# power.net
KiCad netlist of a schematic drawn in Altium Designer
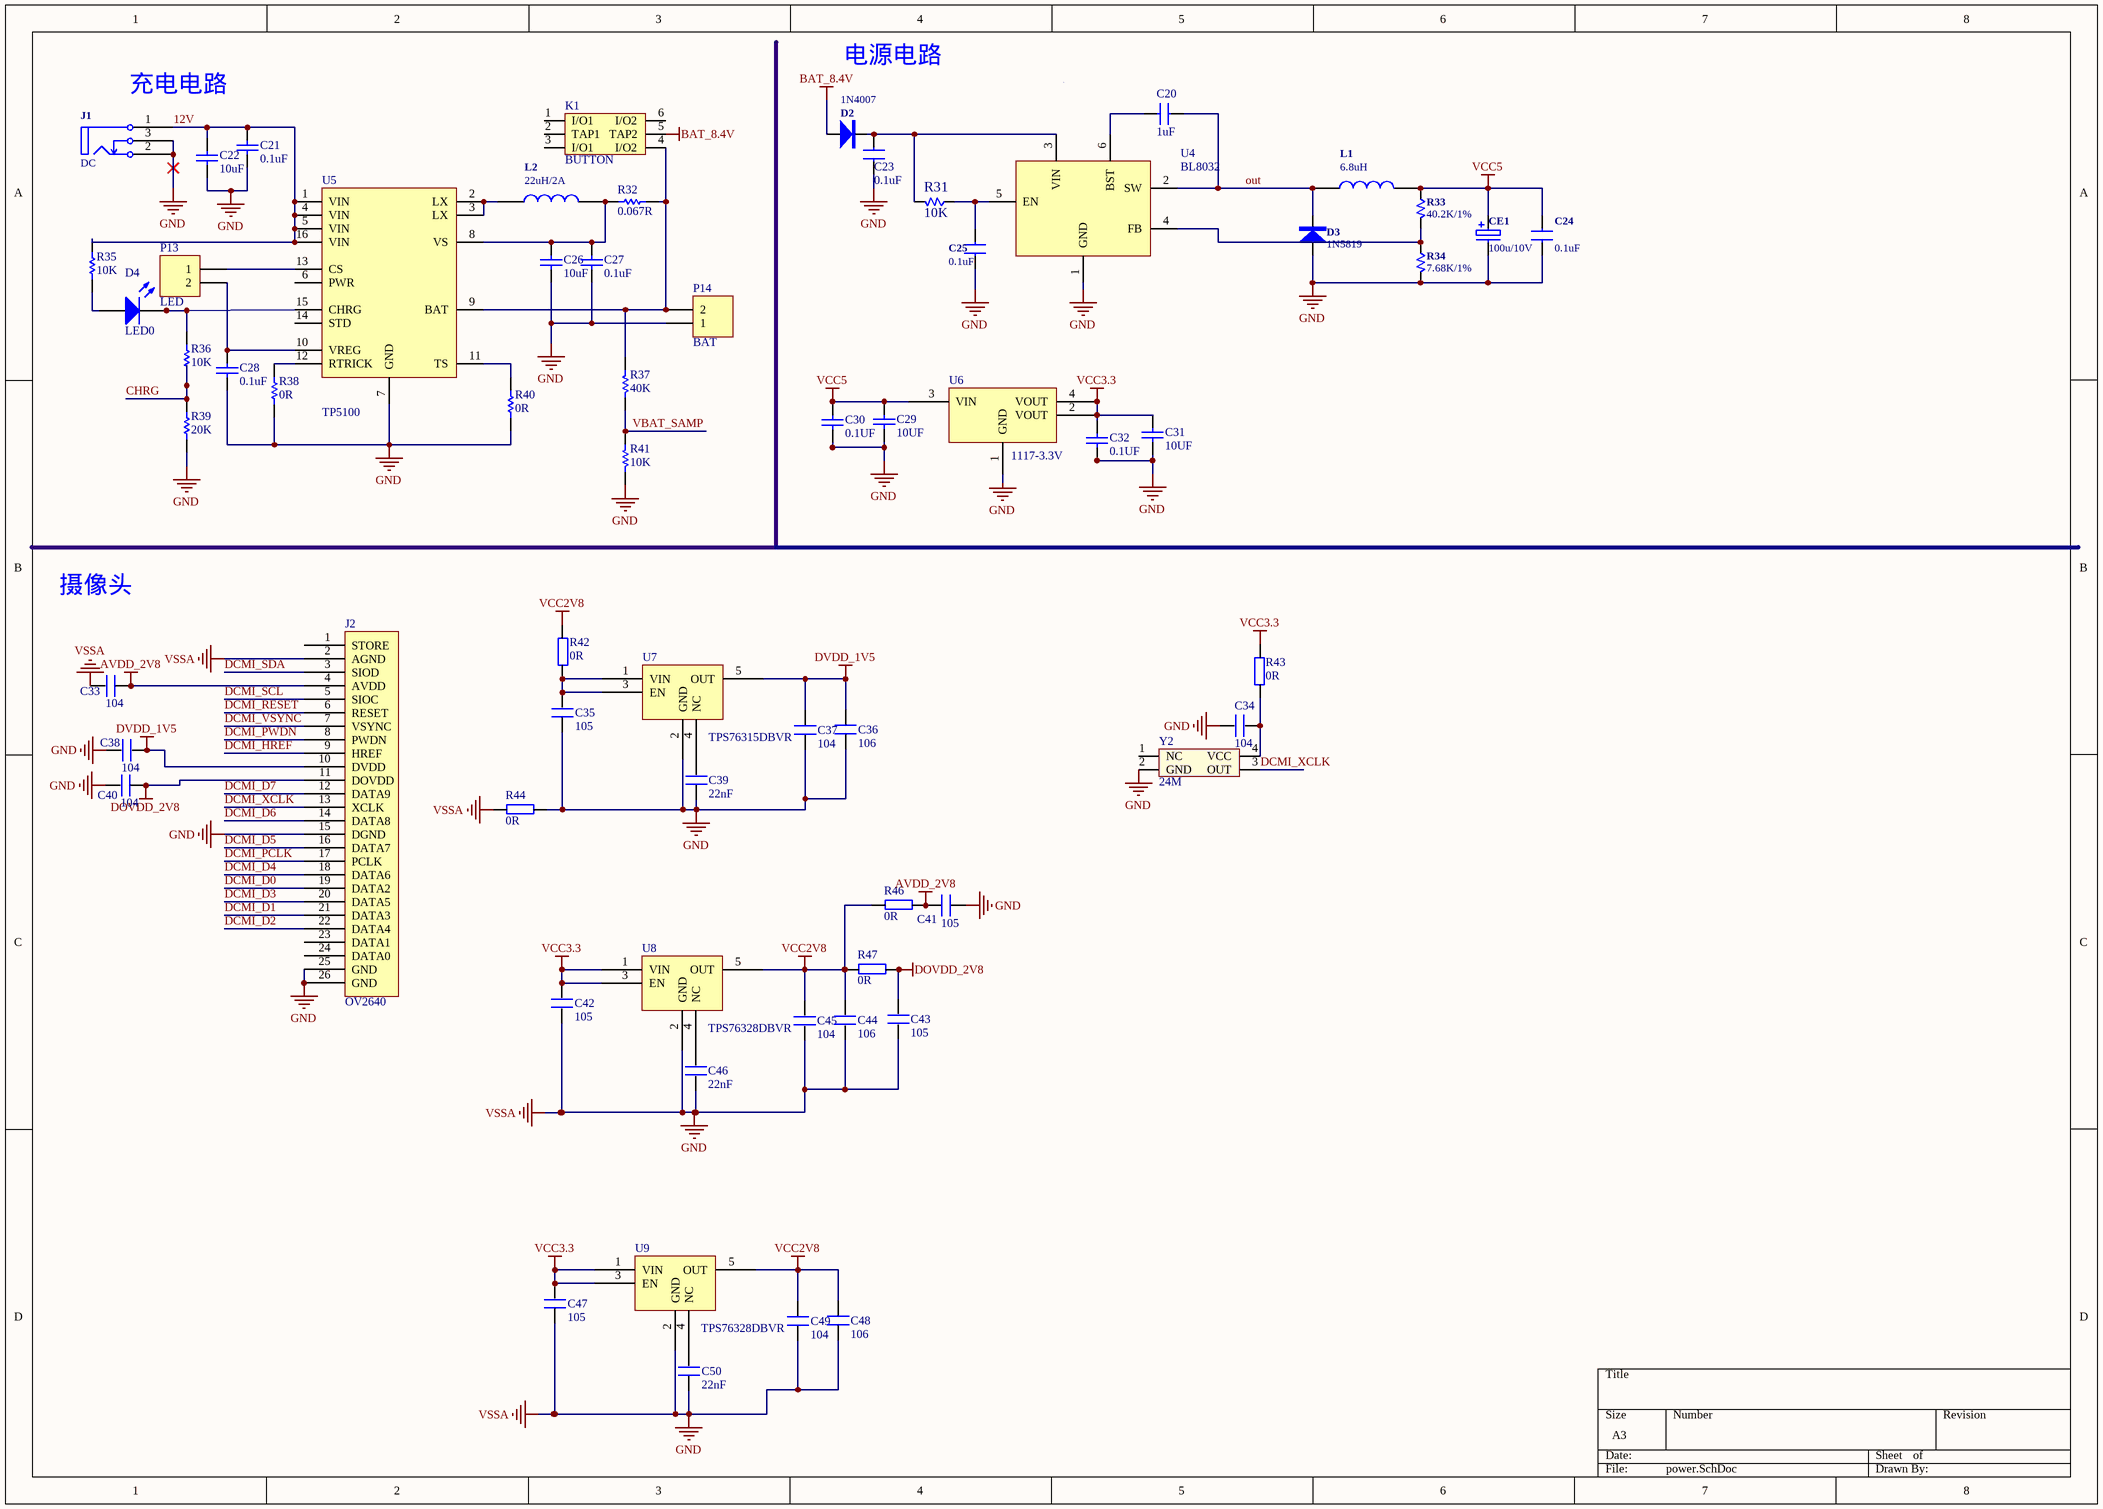
[diagram p0: power.SchDoc]

(export (version "E")
  (design (tool "Eeschema 10.0.6"))
  (components
    (comp (ref "C20")
      (value "1uF")
      (footprint "0603c")
      (description "Capacitor")
      (libsource (lib "") (part "CAP_1"))
    )
    (comp (ref "C21")
      (value "0.1uF")
      (footprint "0603C")
      (description "Capacitor")
      (fields (field (name "PUBLISHER") "Altium Limited"))
      (libsource (lib "STM32") (part "CAP"))
    )
    (comp (ref "C22")
      (value "10uF")
      (footprint "0805C")
      (description "Capacitor")
      (fields (field (name "PUBLISHER") "Altium Limited"))
      (libsource (lib "Miscellaneous Devices") (part "Cap"))
    )
    (comp (ref "C23")
      (value "0.1uF")
      (footprint "C0603")
      (description "Capacitor")
      (libsource (lib "*") (part "CAP"))
    )
    (comp (ref "C24")
      (value "0.1uF")
      (footprint "C0603")
      (description "Capacitor")
      (libsource (lib "*") (part "CAP"))
    )
    (comp (ref "C25")
      (value "0.1uF")
      (footprint "C0603")
      (description "Capacitor")
      (libsource (lib "*") (part "CAP"))
    )
    (comp (ref "C26")
      (value "10uF")
      (footprint "0603C")
      (description "Capacitor")
      (fields (field (name "PUBLISHER") "Altium Limited"))
      (libsource (lib "STM32") (part "CAP"))
    )
    (comp (ref "C27")
      (value "0.1uF")
      (footprint "0603C")
      (description "Capacitor")
      (fields (field (name "PUBLISHER") "Altium Limited"))
      (libsource (lib "STM32") (part "CAP"))
    )
    (comp (ref "C28")
      (value "0.1uF")
      (footprint "0603C")
      (description "Capacitor")
      (fields (field (name "PUBLISHER") "Altium Limited"))
      (libsource (lib "STM32") (part "CAP"))
    )
    (comp (ref "C29")
      (value "10UF")
      (footprint "0603C")
      (description "Capacitor")
      (fields (field (name "Comment") "Cap") (field (name "PUBLISHER") "Altium Limited"))
      (libsource (lib "Miscellaneous Devices") (part "Cap"))
    )
    (comp (ref "C30")
      (value "0.1UF")
      (footprint "0603C")
      (description "Capacitor")
      (fields (field (name "Comment") "Cap") (field (name "PUBLISHER") "Altium Limited"))
      (libsource (lib "Miscellaneous Devices") (part "Cap"))
    )
    (comp (ref "C31")
      (value "10UF")
      (footprint "0603C")
      (description "Capacitor")
      (fields (field (name "Comment") "Cap") (field (name "PUBLISHER") "Altium Limited"))
      (libsource (lib "Miscellaneous Devices") (part "Cap"))
    )
    (comp (ref "C32")
      (value "0.1UF")
      (footprint "0603C")
      (description "Capacitor")
      (fields (field (name "Comment") "Cap") (field (name "PUBLISHER") "Altium Limited"))
      (libsource (lib "Miscellaneous Devices") (part "Cap"))
    )
    (comp (ref "C33") (value "104") (footprint "0603P") (libsource (lib "STM32F429核心板封装库") (part "C")))
    (comp (ref "C34") (value "104") (footprint "0603P") (libsource (lib "STM32F429核心板封装库") (part "C")))
    (comp (ref "C35") (value "105") (footprint "0603P") (libsource (lib "STM32F429核心板封装库") (part "C")))
    (comp (ref "C36") (value "106") (footprint "0603P") (libsource (lib "STM32F429核心板封装库") (part "C")))
    (comp (ref "C37") (value "104") (footprint "0603P") (libsource (lib "STM32F429核心板封装库") (part "C")))
    (comp (ref "C38") (value "104") (footprint "0603P") (libsource (lib "STM32F429核心板封装库") (part "C")))
    (comp (ref "C39") (value "22nF") (footprint "0603P") (libsource (lib "STM32F429核心板封装库") (part "C")))
    (comp (ref "C40") (value "104") (footprint "0603P") (libsource (lib "STM32F429核心板封装库") (part "C")))
    (comp (ref "C41") (value "105") (footprint "0603P") (libsource (lib "STM32F429核心板封装库") (part "C")))
    (comp (ref "C42") (value "105") (footprint "0603P") (libsource (lib "STM32F429核心板封装库") (part "C")))
    (comp (ref "C43") (value "105") (footprint "0603P") (libsource (lib "STM32F429核心板封装库") (part "C")))
    (comp (ref "C44") (value "106") (footprint "0603P") (libsource (lib "STM32F429核心板封装库") (part "C")))
    (comp (ref "C45") (value "104") (footprint "0603P") (libsource (lib "STM32F429核心板封装库") (part "C")))
    (comp (ref "C46") (value "22nF") (footprint "0603P") (libsource (lib "STM32F429核心板封装库") (part "C")))
    (comp (ref "C47") (value "105") (footprint "0603P") (libsource (lib "STM32F429核心板封装库") (part "C")))
    (comp (ref "C48") (value "106") (footprint "0603P") (libsource (lib "STM32F429核心板封装库") (part "C")))
    (comp (ref "C49") (value "104") (footprint "0603P") (libsource (lib "STM32F429核心板封装库") (part "C")))
    (comp (ref "C50") (value "22nF") (footprint "0603P") (libsource (lib "STM32F429核心板封装库") (part "C")))
    (comp (ref "CE1") (value "100u/10V") (footprint "C_195") (libsource (lib "*") (part "CE")))
    (comp (ref "D2")
      (value "1N4007")
      (footprint "DO-214AC")
      (description "Diode")
      (libsource (lib "*") (part "D"))
    )
    (comp (ref "D3")
      (value "1N5819")
      (footprint "DO-214AC")
      (description "Diode")
      (libsource (lib "") (part "D_1"))
    )
    (comp (ref "D4")
      (value "LED0")
      (footprint "0603LED")
      (description "Typical INFRARED GaAs LED")
      (fields (field (name "PUBLISHER") "Altium Limited"))
      (libsource (lib "Miscellaneous Devices") (part "LED0"))
    )
    (comp (ref "J1") (value "DC") (footprint "dc5V") (libsource (lib "*") (part "POWERCON")))
    (comp (ref "J2")
      (value "OV2640")
      (footprint "wifi_car:OV2640")
      (libsource (lib "wifi_car") (part "OV2640"))
    )
    (comp (ref "K1")
      (value "BUTTON")
      (footprint "BTN8.5*8.5")
      (libsource (lib "阿波罗STM32F4&F7底板封装库") (part "BUTTON"))
    )
    (comp (ref "L1") (value "6.8uH") (footprint "WE_PD") (libsource (lib "*") (part "INDUCTOR")))
    (comp (ref "L2") (value "22uH/2A") (footprint "WE_PD") (libsource (lib "*") (part "INDUCTOR")))
    (comp (ref "P13")
      (value "LED")
      (footprint "SIP2")
      (description "Header, 2-Pin")
      (fields (field (name "PUBLISHER") "Altium Limited"))
      (libsource (lib "Miscellaneous Connectors") (part "Header 2"))
    )
    (comp (ref "P14")
      (value "BAT")
      (footprint "CON2")
      (description "Header, 2-Pin")
      (fields (field (name "PUBLISHER") "Altium Limited"))
      (libsource (lib "") (part "Header 2_1"))
    )
    (comp (ref "R31")
      (value "10K")
      (footprint "R0603")
      (description "Resistor")
      (libsource (lib "*") (part "R"))
    )
    (comp (ref "R32")
      (value "0.067R")
      (footprint "1206")
      (description "Resistor")
      (fields (field (name "PUBLISHER") "Altium Limited"))
      (libsource (lib "Miscellaneous Devices") (part "Res1"))
    )
    (comp (ref "R33")
      (value "40.2K/1%")
      (footprint "R0603")
      (description "Resistor")
      (libsource (lib "CONNECTOR") (part "R"))
    )
    (comp (ref "R34")
      (value "7.68K/1%")
      (footprint "R0603")
      (description "Resistor")
      (libsource (lib "CONNECTOR") (part "R"))
    )
    (comp (ref "R35")
      (value "10K")
      (footprint "0603C")
      (description "Resistor")
      (fields (field (name "PUBLISHER") "Altium Limited"))
      (libsource (lib "Miscellaneous Devices") (part "Res1"))
    )
    (comp (ref "R36")
      (value "10K")
      (footprint "0603C")
      (description "Resistor")
      (fields (field (name "PUBLISHER") "Altium Limited"))
      (libsource (lib "Miscellaneous Devices") (part "Res1"))
    )
    (comp (ref "R37")
      (value "40K")
      (footprint "0603R")
      (description "Resistor")
      (fields (field (name "PUBLISHER") "Altium Limited"))
      (libsource (lib "STM32") (part "res1"))
    )
    (comp (ref "R38")
      (value "0R")
      (footprint "0603C")
      (description "Resistor")
      (fields (field (name "PUBLISHER") "Altium Limited"))
      (libsource (lib "Miscellaneous Devices") (part "Res1"))
    )
    (comp (ref "R39")
      (value "20K")
      (footprint "0603C")
      (description "Resistor")
      (fields (field (name "PUBLISHER") "Altium Limited"))
      (libsource (lib "Miscellaneous Devices") (part "Res1"))
    )
    (comp (ref "R40")
      (value "0R")
      (footprint "0603R")
      (description "Resistor")
      (fields (field (name "PUBLISHER") "Altium Limited"))
      (libsource (lib "Miscellaneous Devices") (part "Res1"))
    )
    (comp (ref "R41")
      (value "10K")
      (footprint "0603R")
      (description "Resistor")
      (fields (field (name "PUBLISHER") "Altium Limited"))
      (libsource (lib "STM32") (part "res1"))
    )
    (comp (ref "R42") (value "0R") (footprint "0603P") (libsource (lib "STM32F429核心板封装库") (part "R")))
    (comp (ref "R43") (value "0R") (footprint "0603P") (libsource (lib "STM32F429核心板封装库") (part "R")))
    (comp (ref "R44") (value "0R") (footprint "0603P") (libsource (lib "STM32F429核心板封装库") (part "R")))
    (comp (ref "R46") (value "0R") (footprint "0603P") (libsource (lib "STM32F429核心板封装库") (part "R")))
    (comp (ref "R47") (value "0R") (footprint "0603P") (libsource (lib "STM32F429核心板封装库") (part "R")))
    (comp (ref "U4")
      (value "BL8032")
      (footprint "SOT23-6")
      (description "Diode Bridge")
      (libsource (lib "F718_XP_V1.0") (part "BL8032"))
    )
    (comp (ref "U5")
      (value "TP5100")
      (footprint "QFN16(4*4)")
      (description "Capacitor")
      (fields (field (name "PUBLISHER") "Altium Limited"))
      (libsource (lib "ZNXC_V1.0") (part "TP5100"))
    )
    (comp (ref "U6")
      (value "1117-3.3V")
      (footprint "SOT223")
      (description "LDO")
      (fields (field (name "PUBLISHER") "Altium Limited"))
      (libsource (lib "TS-QBF-05") (part "1117"))
    )
    (comp (ref "U7")
      (value "TPS76315DBVR")
      (footprint "wifi_car:TPS763")
      (libsource (lib "wifi_car") (part "TPS763  SOT23-5"))
    )
    (comp (ref "U8")
      (value "TPS76328DBVR")
      (footprint "wifi_car:TPS763")
      (description "TPS76315DBVR")
      (libsource (lib "wifi_car") (part "TPS763  SOT23-5"))
    )
    (comp (ref "U9")
      (value "TPS76328DBVR")
      (footprint "wifi_car:TPS763")
      (description "TPS76315DBVR")
      (libsource (lib "wifi_car") (part "TPS763  SOT23-5"))
    )
    (comp (ref "Y2") (value "24M") (footprint "wifi_car:XTAL_S") (libsource (lib "wifi_car") (part "XTAL_S")))
  )
  (nets
    (net (code "1") (name "/12V") (class "Default")
      (node (ref "C21") (pin "2") (pinfunction "2_2") (pintype "passive"))
      (node (ref "C22") (pin "1") (pinfunction "1_1") (pintype "passive"))
      (node (ref "J1") (pin "1") (pintype "passive"))
      (node (ref "R35") (pin "2") (pinfunction "2_2") (pintype "passive"))
      (node (ref "U5") (pin "1") (pinfunction "VIN_1") (pintype "passive"))
      (node (ref "U5") (pin "16") (pinfunction "VIN_16") (pintype "passive"))
      (node (ref "U5") (pin "4") (pinfunction "VIN_4") (pintype "passive"))
      (node (ref "U5") (pin "5") (pinfunction "VIN_5") (pintype "passive"))
    )
    (net (code "2") (name "/CHRG") (class "Default")
      (node (ref "R36") (pin "1") (pinfunction "1_1") (pintype "passive"))
      (node (ref "R39") (pin "2") (pinfunction "2_2") (pintype "passive"))
    )
    (net (code "3") (name "/DCMI_D0") (class "Default")
      (node (ref "J2") (pin "19") (pinfunction "DATA2_19") (pintype "passive"))
    )
    (net (code "4") (name "/DCMI_D1") (class "Default")
      (node (ref "J2") (pin "21") (pinfunction "DATA3_21") (pintype "passive"))
    )
    (net (code "5") (name "/DCMI_D2") (class "Default")
      (node (ref "J2") (pin "22") (pinfunction "DATA4_22") (pintype "passive"))
    )
    (net (code "6") (name "/DCMI_D3") (class "Default")
      (node (ref "J2") (pin "20") (pinfunction "DATA5_20") (pintype "passive"))
    )
    (net (code "7") (name "/DCMI_D4") (class "Default")
      (node (ref "J2") (pin "18") (pinfunction "DATA6_18") (pintype "passive"))
    )
    (net (code "8") (name "/DCMI_D5") (class "Default")
      (node (ref "J2") (pin "16") (pinfunction "DATA7_16") (pintype "passive"))
    )
    (net (code "9") (name "/DCMI_D6") (class "Default")
      (node (ref "J2") (pin "14") (pinfunction "DATA8_14") (pintype "passive"))
    )
    (net (code "10") (name "/DCMI_D7") (class "Default")
      (node (ref "J2") (pin "12") (pinfunction "DATA9_12") (pintype "passive"))
    )
    (net (code "11") (name "/DCMI_HREF") (class "Default")
      (node (ref "J2") (pin "9") (pinfunction "HREF_9") (pintype "passive"))
    )
    (net (code "12") (name "/DCMI_PCLK") (class "Default")
      (node (ref "J2") (pin "17") (pinfunction "PCLK_17") (pintype "passive"))
    )
    (net (code "13") (name "/DCMI_PWDN") (class "Default")
      (node (ref "J2") (pin "8") (pinfunction "PWDN_8") (pintype "passive"))
    )
    (net (code "14") (name "/DCMI_RESET") (class "Default")
      (node (ref "J2") (pin "6") (pinfunction "RESET_6") (pintype "passive"))
    )
    (net (code "15") (name "/DCMI_SCL") (class "Default")
      (node (ref "J2") (pin "5") (pinfunction "SIOC_5") (pintype "passive"))
    )
    (net (code "16") (name "/DCMI_SDA") (class "Default")
      (node (ref "J2") (pin "3") (pinfunction "SIOD_3") (pintype "passive"))
    )
    (net (code "17") (name "/DCMI_VSYNC") (class "Default")
      (node (ref "J2") (pin "7") (pinfunction "VSYNC_7") (pintype "passive"))
    )
    (net (code "18") (name "/DCMI_XCLK") (class "Default")
      (node (ref "J2") (pin "13") (pinfunction "XCLK_13") (pintype "passive"))
      (node (ref "Y2") (pin "3") (pinfunction "OUT_3") (pintype "passive"))
    )
    (net (code "19") (name "/VBAT_SAMP") (class "Default")
      (node (ref "R37") (pin "2") (pinfunction "2_2") (pintype "passive"))
      (node (ref "R41") (pin "1") (pinfunction "1_1") (pintype "passive"))
    )
    (net (code "20") (name "/out") (class "Default")
      (node (ref "C20") (pin "2") (pinfunction "2_2") (pintype "passive"))
      (node (ref "D3") (pin "2") (pinfunction "K_2") (pintype "passive"))
      (node (ref "L1") (pin "1") (pinfunction "1_1") (pintype "passive"))
      (node (ref "U4") (pin "2") (pinfunction "SW_2") (pintype "passive"))
    )
    (net (code "21") (name "AVDD_2V8") (class "Default")
      (node (ref "C33") (pin "1") (pintype "passive"))
      (node (ref "C41") (pin "1") (pintype "passive"))
      (node (ref "J2") (pin "4") (pinfunction "AVDD_4") (pintype "passive"))
      (node (ref "R46") (pin "1") (pintype "passive"))
    )
    (net (code "22") (name "BAT_8.4V") (class "Default")
      (node (ref "D2") (pin "1") (pinfunction "A_1") (pintype "passive"))
      (node (ref "K1") (pin "5") (pinfunction "TAP2_5") (pintype "passive"))
    )
    (net (code "23") (name "DOVDD_2V8") (class "Default")
      (node (ref "C40") (pin "1") (pintype "passive"))
      (node (ref "C43") (pin "2") (pintype "passive"))
      (node (ref "J2") (pin "11") (pinfunction "DOVDD_11") (pintype "passive"))
      (node (ref "R47") (pin "1") (pintype "passive"))
    )
    (net (code "24") (name "DVDD_1V5") (class "Default")
      (node (ref "C36") (pin "2") (pintype "passive"))
      (node (ref "C37") (pin "2") (pintype "passive"))
      (node (ref "C38") (pin "1") (pintype "passive"))
      (node (ref "J2") (pin "10") (pinfunction "DVDD_10") (pintype "passive"))
      (node (ref "U7") (pin "5") (pinfunction "OUT_5") (pintype "passive"))
    )
    (net (code "25") (name "GND") (class "Default")
      (node (ref "C21") (pin "1") (pinfunction "1_1") (pintype "passive"))
      (node (ref "C22") (pin "2") (pinfunction "2_2") (pintype "passive"))
      (node (ref "C23") (pin "2") (pinfunction "2_2") (pintype "passive"))
      (node (ref "C24") (pin "2") (pinfunction "2_2") (pintype "passive"))
      (node (ref "C25") (pin "2") (pinfunction "2_2") (pintype "passive"))
      (node (ref "C26") (pin "1") (pinfunction "1_1") (pintype "passive"))
      (node (ref "C27") (pin "1") (pinfunction "1_1") (pintype "passive"))
      (node (ref "C28") (pin "1") (pinfunction "1_1") (pintype "passive"))
      (node (ref "C29") (pin "2") (pinfunction "2_2") (pintype "passive"))
      (node (ref "C30") (pin "2") (pinfunction "2_2") (pintype "passive"))
      (node (ref "C31") (pin "2") (pinfunction "2_2") (pintype "passive"))
      (node (ref "C32") (pin "2") (pinfunction "2_2") (pintype "passive"))
      (node (ref "C33") (pin "2") (pintype "passive"))
      (node (ref "C34") (pin "2") (pintype "passive"))
      (node (ref "C35") (pin "1") (pintype "passive"))
      (node (ref "C36") (pin "1") (pintype "passive"))
      (node (ref "C37") (pin "1") (pintype "passive"))
      (node (ref "C38") (pin "2") (pintype "passive"))
      (node (ref "C39") (pin "1") (pintype "passive"))
      (node (ref "C40") (pin "2") (pintype "passive"))
      (node (ref "C41") (pin "2") (pintype "passive"))
      (node (ref "C42") (pin "1") (pintype "passive"))
      (node (ref "C43") (pin "1") (pintype "passive"))
      (node (ref "C44") (pin "1") (pintype "passive"))
      (node (ref "C45") (pin "1") (pintype "passive"))
      (node (ref "C46") (pin "1") (pintype "passive"))
      (node (ref "C47") (pin "1") (pintype "passive"))
      (node (ref "C48") (pin "1") (pintype "passive"))
      (node (ref "C49") (pin "1") (pintype "passive"))
      (node (ref "C50") (pin "1") (pintype "passive"))
      (node (ref "CE1") (pin "2") (pintype "passive"))
      (node (ref "D3") (pin "1") (pinfunction "A_1") (pintype "passive"))
      (node (ref "J1") (pin "2") (pintype "passive"))
      (node (ref "J1") (pin "3") (pintype "passive"))
      (node (ref "J2") (pin "15") (pinfunction "DGND_15") (pintype "passive"))
      (node (ref "J2") (pin "2") (pinfunction "AGND_2") (pintype "passive"))
      (node (ref "J2") (pin "25") (pinfunction "GND_25") (pintype "passive"))
      (node (ref "J2") (pin "26") (pinfunction "GND_26") (pintype "passive"))
      (node (ref "P14") (pin "1") (pinfunction "1_1") (pintype "passive"))
      (node (ref "R34") (pin "2") (pinfunction "2_2") (pintype "passive"))
      (node (ref "R38") (pin "1") (pinfunction "1_1") (pintype "passive"))
      (node (ref "R39") (pin "1") (pinfunction "1_1") (pintype "passive"))
      (node (ref "R40") (pin "1") (pinfunction "1_1") (pintype "passive"))
      (node (ref "R41") (pin "2") (pinfunction "2_2") (pintype "passive"))
      (node (ref "R44") (pin "1") (pintype "passive"))
      (node (ref "R44") (pin "2") (pintype "passive"))
      (node (ref "U4") (pin "1") (pinfunction "GND_1") (pintype "passive"))
      (node (ref "U5") (pin "7") (pinfunction "GND_7") (pintype "passive"))
      (node (ref "U6") (pin "1") (pinfunction "GND_1") (pintype "passive"))
      (node (ref "U7") (pin "2") (pinfunction "GND_2") (pintype "passive"))
      (node (ref "U8") (pin "2") (pinfunction "GND_2") (pintype "passive"))
      (node (ref "U9") (pin "2") (pinfunction "GND_2") (pintype "passive"))
      (node (ref "Y2") (pin "2") (pinfunction "GND_2") (pintype "passive"))
    )
    (net (code "26") (name "Net-(D2-K)") (class "Default")
      (node (ref "C23") (pin "1") (pinfunction "1_1") (pintype "passive"))
      (node (ref "D2") (pin "2") (pinfunction "K_2") (pintype "passive"))
      (node (ref "R31") (pin "2") (pinfunction "2_2") (pintype "passive"))
      (node (ref "U4") (pin "3") (pinfunction "VIN_3") (pintype "passive"))
    )
    (net (code "27") (name "Net-(D4-A)") (class "Default")
      (node (ref "D4") (pin "1") (pinfunction "A_1") (pintype "passive"))
      (node (ref "R35") (pin "1") (pinfunction "1_1") (pintype "passive"))
    )
    (net (code "28") (name "Net-(D4-K)") (class "Default")
      (node (ref "D4") (pin "2") (pinfunction "K_2") (pintype "passive"))
      (node (ref "R36") (pin "2") (pinfunction "2_2") (pintype "passive"))
      (node (ref "U5") (pin "15") (pinfunction "CHRG_15") (pintype "passive"))
    )
    (net (code "29") (name "Net-(L2-Pad1)") (class "Default")
      (node (ref "L2") (pin "1") (pinfunction "1_1") (pintype "passive"))
      (node (ref "U5") (pin "2") (pinfunction "LX_2") (pintype "passive"))
      (node (ref "U5") (pin "3") (pinfunction "LX_3") (pintype "passive"))
    )
    (net (code "30") (name "Net-(U4-BST)") (class "Default")
      (node (ref "C20") (pin "1") (pinfunction "1_1") (pintype "passive"))
      (node (ref "U4") (pin "6") (pinfunction "BST_6") (pintype "passive"))
    )
    (net (code "31") (name "Net-(U4-EN)") (class "Default")
      (node (ref "C25") (pin "1") (pinfunction "1_1") (pintype "passive"))
      (node (ref "R31") (pin "1") (pinfunction "1_1") (pintype "passive"))
      (node (ref "U4") (pin "5") (pinfunction "EN_5") (pintype "passive"))
    )
    (net (code "32") (name "Net-(U4-FB)") (class "Default")
      (node (ref "R33") (pin "2") (pinfunction "2_2") (pintype "passive"))
      (node (ref "R34") (pin "1") (pinfunction "1_1") (pintype "passive"))
      (node (ref "U4") (pin "4") (pinfunction "FB_4") (pintype "passive"))
    )
    (net (code "33") (name "Net-(U5-BAT)") (class "Default")
      (node (ref "K1") (pin "4") (pinfunction "I/O2_4") (pintype "passive"))
      (node (ref "P14") (pin "2") (pinfunction "2_2") (pintype "passive"))
      (node (ref "R32") (pin "1") (pinfunction "1_1") (pintype "passive"))
      (node (ref "R37") (pin "1") (pinfunction "1_1") (pintype "passive"))
      (node (ref "U5") (pin "9") (pinfunction "BAT_9") (pintype "passive"))
    )
    (net (code "34") (name "Net-(U5-CS)") (class "Default")
      (node (ref "P13") (pin "1") (pinfunction "1_1") (pintype "passive"))
      (node (ref "U5") (pin "13") (pinfunction "CS_13") (pintype "passive"))
    )
    (net (code "35") (name "Net-(U5-RTRICK)") (class "Default")
      (node (ref "R38") (pin "2") (pinfunction "2_2") (pintype "passive"))
      (node (ref "U5") (pin "12") (pinfunction "RTRICK_12") (pintype "passive"))
    )
    (net (code "36") (name "Net-(U5-TS)") (class "Default")
      (node (ref "R40") (pin "2") (pinfunction "2_2") (pintype "passive"))
      (node (ref "U5") (pin "11") (pinfunction "TS_11") (pintype "passive"))
    )
    (net (code "37") (name "Net-(U5-VREG)") (class "Default")
      (node (ref "C28") (pin "2") (pinfunction "2_2") (pintype "passive"))
      (node (ref "P13") (pin "2") (pinfunction "2_2") (pintype "passive"))
      (node (ref "U5") (pin "10") (pinfunction "VREG_10") (pintype "passive"))
    )
    (net (code "38") (name "Net-(U5-VS)") (class "Default")
      (node (ref "C26") (pin "2") (pinfunction "2_2") (pintype "passive"))
      (node (ref "C27") (pin "2") (pinfunction "2_2") (pintype "passive"))
      (node (ref "L2") (pin "2") (pinfunction "2_2") (pintype "passive"))
      (node (ref "R32") (pin "2") (pinfunction "2_2") (pintype "passive"))
      (node (ref "U5") (pin "8") (pinfunction "VS_8") (pintype "passive"))
    )
    (net (code "39") (name "Net-(U7-EN)") (class "Default")
      (node (ref "C35") (pin "2") (pintype "passive"))
      (node (ref "R42") (pin "1") (pintype "passive"))
      (node (ref "U7") (pin "1") (pinfunction "VIN_1") (pintype "passive"))
      (node (ref "U7") (pin "3") (pinfunction "EN_3") (pintype "passive"))
    )
    (net (code "40") (name "Net-(U7-NC)") (class "Default")
      (node (ref "C39") (pin "2") (pintype "passive"))
      (node (ref "U7") (pin "4") (pinfunction "NC_4") (pintype "passive"))
    )
    (net (code "41") (name "Net-(U8-NC)") (class "Default")
      (node (ref "C46") (pin "2") (pintype "passive"))
      (node (ref "U8") (pin "4") (pinfunction "NC_4") (pintype "passive"))
    )
    (net (code "42") (name "Net-(U9-NC)") (class "Default")
      (node (ref "C50") (pin "2") (pintype "passive"))
      (node (ref "U9") (pin "4") (pinfunction "NC_4") (pintype "passive"))
    )
    (net (code "43") (name "Net-(Y2-VCC)") (class "Default")
      (node (ref "C34") (pin "1") (pintype "passive"))
      (node (ref "R43") (pin "2") (pintype "passive"))
      (node (ref "Y2") (pin "4") (pinfunction "VCC_4") (pintype "passive"))
    )
    (net (code "44") (name "VCC2V8") (class "Default")
      (node (ref "C44") (pin "2") (pintype "passive"))
      (node (ref "C45") (pin "2") (pintype "passive"))
      (node (ref "C48") (pin "2") (pintype "passive"))
      (node (ref "C49") (pin "2") (pintype "passive"))
      (node (ref "R42") (pin "2") (pintype "passive"))
      (node (ref "R46") (pin "2") (pintype "passive"))
      (node (ref "R47") (pin "2") (pintype "passive"))
      (node (ref "U8") (pin "5") (pinfunction "OUT_5") (pintype "passive"))
      (node (ref "U9") (pin "5") (pinfunction "OUT_5") (pintype "passive"))
    )
    (net (code "45") (name "VCC3.3") (class "Default")
      (node (ref "C31") (pin "1") (pinfunction "1_1") (pintype "passive"))
      (node (ref "C32") (pin "1") (pinfunction "1_1") (pintype "passive"))
      (node (ref "C42") (pin "2") (pintype "passive"))
      (node (ref "C47") (pin "2") (pintype "passive"))
      (node (ref "R43") (pin "1") (pintype "passive"))
      (node (ref "U6") (pin "2") (pinfunction "VOUT_2") (pintype "passive"))
      (node (ref "U6") (pin "4") (pinfunction "VOUT_4") (pintype "passive"))
      (node (ref "U8") (pin "1") (pinfunction "VIN_1") (pintype "passive"))
      (node (ref "U8") (pin "3") (pinfunction "EN_3") (pintype "passive"))
      (node (ref "U9") (pin "1") (pinfunction "VIN_1") (pintype "passive"))
      (node (ref "U9") (pin "3") (pinfunction "EN_3") (pintype "passive"))
    )
    (net (code "46") (name "VCC5") (class "Default")
      (node (ref "C24") (pin "1") (pinfunction "1_1") (pintype "passive"))
      (node (ref "C29") (pin "1") (pinfunction "1_1") (pintype "passive"))
      (node (ref "C30") (pin "1") (pinfunction "1_1") (pintype "passive"))
      (node (ref "CE1") (pin "1") (pintype "passive"))
      (node (ref "L1") (pin "2") (pinfunction "2_2") (pintype "passive"))
      (node (ref "R33") (pin "1") (pinfunction "1_1") (pintype "passive"))
      (node (ref "U6") (pin "3") (pinfunction "VIN_3") (pintype "passive"))
    )
    (net (code "47") (name "unconnected-(J2-DATA0-Pad24)") (class "Default")
      (node (ref "J2") (pin "24") (pinfunction "DATA0_24") (pintype "passive"))
    )
    (net (code "48") (name "unconnected-(J2-DATA1-Pad23)") (class "Default")
      (node (ref "J2") (pin "23") (pinfunction "DATA1_23") (pintype "passive"))
    )
    (net (code "49") (name "unconnected-(J2-STORE-Pad1)") (class "Default")
      (node (ref "J2") (pin "1") (pinfunction "STORE_1") (pintype "passive"))
    )
    (net (code "50") (name "unconnected-(K1-I{slash}O1-Pad1)") (class "Default")
      (node (ref "K1") (pin "1") (pinfunction "I/O1_1") (pintype "passive"))
    )
    (net (code "51") (name "unconnected-(K1-I{slash}O1-Pad3)") (class "Default")
      (node (ref "K1") (pin "3") (pinfunction "I/O1_3") (pintype "passive"))
    )
    (net (code "52") (name "unconnected-(K1-I{slash}O2-Pad6)") (class "Default")
      (node (ref "K1") (pin "6") (pinfunction "I/O2_6") (pintype "passive"))
    )
    (net (code "53") (name "unconnected-(K1-TAP1-Pad2)") (class "Default")
      (node (ref "K1") (pin "2") (pinfunction "TAP1_2") (pintype "passive"))
    )
    (net (code "54") (name "unconnected-(U5-PWR-Pad6)") (class "Default")
      (node (ref "U5") (pin "6") (pinfunction "PWR_6") (pintype "passive"))
    )
    (net (code "55") (name "unconnected-(U5-STD-Pad14)") (class "Default")
      (node (ref "U5") (pin "14") (pinfunction "STD_14") (pintype "passive"))
    )
    (net (code "56") (name "unconnected-(Y2-NC-Pad1)") (class "Default")
      (node (ref "Y2") (pin "1") (pinfunction "NC_1") (pintype "passive"))
    )
  )
)
